# Power.net
KiCad netlist of a schematic drawn in Altium Designer
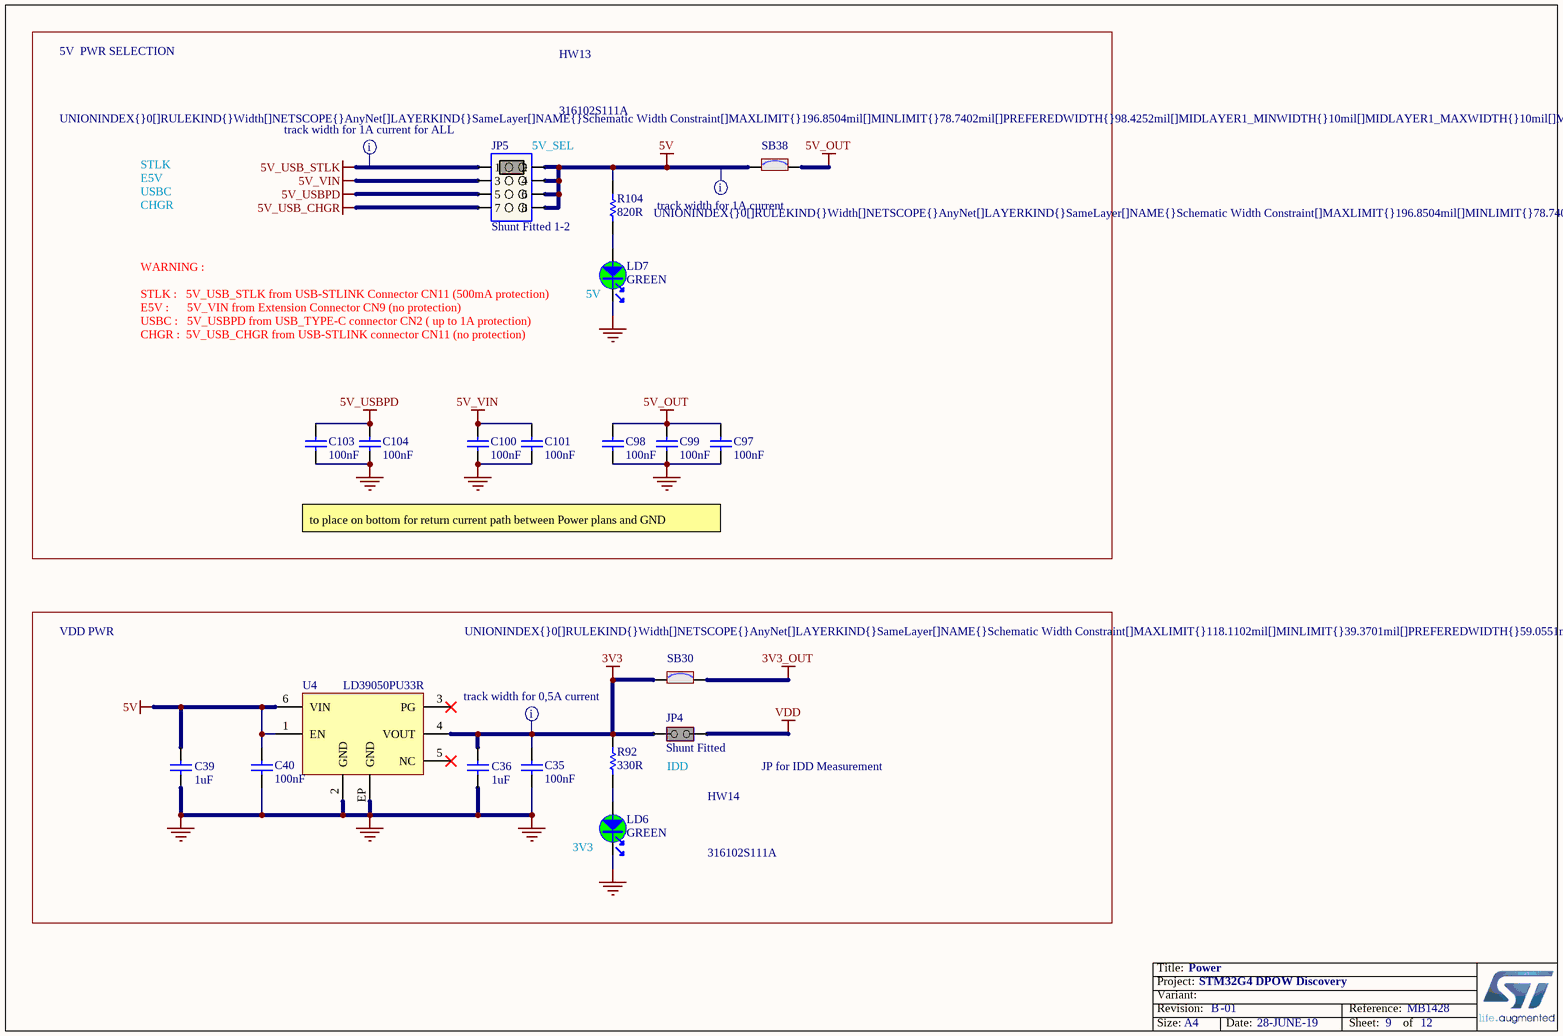
[diagram p0: Power.SchDoc]

(export (version "E")
  (design (tool "Eeschema 10.0.6"))
  (components
    (comp (ref "C35")
      (value "100nF")
      (footprint "C0402")
      (description "Capacitor, MLCC, 100nF, 16V, X7R, 10%, 0402, T=0,5mm")
      (fields
        (field (name "INTERNAL_PART_NUMBER") "MCD-00102")
        (field (name "MANUFACTURER_PART_NUMBER") "CC0402KRX7R7BB104")
        (field (name "PROVIDED_BY") "SUBCO")
      )
      (libsource (lib "MCD_PARTS_database") (part "Capacitor"))
    )
    (comp (ref "C36")
      (value "1uF")
      (footprint "C0603")
      (description "Capacitor, MLCC, 1uF, 16V, X5R, 10%, 0603, T=0,8mm")
      (fields
        (field (name "INTERNAL_PART_NUMBER") "MCD-00010")
        (field (name "MANUFACTURER_PART_NUMBER") "CC0603KRX5R7BB105")
        (field (name "PROVIDED_BY") "SUBCO")
      )
      (libsource (lib "MCD_PARTS_database") (part "Capacitor"))
    )
    (comp (ref "C39")
      (value "1uF")
      (footprint "C0603")
      (description "Capacitor, MLCC, 1uF, 16V, X5R, 10%, 0603, T=0,8mm")
      (fields
        (field (name "INTERNAL_PART_NUMBER") "MCD-00010")
        (field (name "MANUFACTURER_PART_NUMBER") "CC0603KRX5R7BB105")
        (field (name "PROVIDED_BY") "SUBCO")
      )
      (libsource (lib "MCD_PARTS_database") (part "Capacitor"))
    )
    (comp (ref "C40")
      (value "100nF")
      (footprint "C0402")
      (description "Capacitor, MLCC, 100nF, 16V, X7R, 10%, 0402, T=0,5mm")
      (fields
        (field (name "INTERNAL_PART_NUMBER") "MCD-00102")
        (field (name "MANUFACTURER_PART_NUMBER") "CC0402KRX7R7BB104")
        (field (name "PROVIDED_BY") "SUBCO")
      )
      (libsource (lib "MCD_PARTS_database") (part "Capacitor"))
    )
    (comp (ref "C97")
      (value "100nF")
      (footprint "C0402")
      (description "Capacitor, MLCC, 100nF, 16V, X7R, 10%, 0402, T=0,5mm")
      (fields
        (field (name "INTERNAL_PART_NUMBER") "MCD-00102")
        (field (name "MANUFACTURER_PART_NUMBER") "CC0402KRX7R7BB104")
        (field (name "PROVIDED_BY") "SUBCO")
      )
      (libsource (lib "MCD_PARTS_database") (part "Capacitor"))
    )
    (comp (ref "C98")
      (value "100nF")
      (footprint "C0402")
      (description "Capacitor, MLCC, 100nF, 16V, X7R, 10%, 0402, T=0,5mm")
      (fields
        (field (name "INTERNAL_PART_NUMBER") "MCD-00102")
        (field (name "MANUFACTURER_PART_NUMBER") "CC0402KRX7R7BB104")
        (field (name "PROVIDED_BY") "SUBCO")
      )
      (libsource (lib "MCD_PARTS_database") (part "Capacitor"))
    )
    (comp (ref "C99")
      (value "100nF")
      (footprint "C0402")
      (description "Capacitor, MLCC, 100nF, 16V, X7R, 10%, 0402, T=0,5mm")
      (fields
        (field (name "INTERNAL_PART_NUMBER") "MCD-00102")
        (field (name "MANUFACTURER_PART_NUMBER") "CC0402KRX7R7BB104")
        (field (name "PROVIDED_BY") "SUBCO")
      )
      (libsource (lib "MCD_PARTS_database") (part "Capacitor"))
    )
    (comp (ref "C100")
      (value "100nF")
      (footprint "C0402")
      (description "Capacitor, MLCC, 100nF, 16V, X7R, 10%, 0402, T=0,5mm")
      (fields
        (field (name "INTERNAL_PART_NUMBER") "MCD-00102")
        (field (name "MANUFACTURER_PART_NUMBER") "CC0402KRX7R7BB104")
        (field (name "PROVIDED_BY") "SUBCO")
      )
      (libsource (lib "MCD_PARTS_database") (part "Capacitor"))
    )
    (comp (ref "C101")
      (value "100nF")
      (footprint "C0402")
      (description "Capacitor, MLCC, 100nF, 16V, X7R, 10%, 0402, T=0,5mm")
      (fields
        (field (name "INTERNAL_PART_NUMBER") "MCD-00102")
        (field (name "MANUFACTURER_PART_NUMBER") "CC0402KRX7R7BB104")
        (field (name "PROVIDED_BY") "SUBCO")
      )
      (libsource (lib "MCD_PARTS_database") (part "Capacitor"))
    )
    (comp (ref "C103")
      (value "100nF")
      (footprint "C0402")
      (description "Capacitor, MLCC, 100nF, 16V, X7R, 10%, 0402, T=0,5mm")
      (fields
        (field (name "INTERNAL_PART_NUMBER") "MCD-00102")
        (field (name "MANUFACTURER_PART_NUMBER") "CC0402KRX7R7BB104")
        (field (name "PROVIDED_BY") "SUBCO")
      )
      (libsource (lib "MCD_PARTS_database") (part "Capacitor"))
    )
    (comp (ref "C104")
      (value "100nF")
      (footprint "C0402")
      (description "Capacitor, MLCC, 100nF, 16V, X7R, 10%, 0402, T=0,5mm")
      (fields
        (field (name "INTERNAL_PART_NUMBER") "MCD-00102")
        (field (name "MANUFACTURER_PART_NUMBER") "CC0402KRX7R7BB104")
        (field (name "PROVIDED_BY") "SUBCO")
      )
      (libsource (lib "MCD_PARTS_database") (part "Capacitor"))
    )
    (comp (ref "HW13")
      (value "316102S111A")
      (description "Jumper, height 6mm, Black, 2.54mm, 3A, 20 mohm, open")
      (fields
        (field (name "INTERNAL_PART_NUMBER") "MCD-01849")
        (field (name "MANUFACTURER") "JIUBABA")
        (field (name "PROVIDED_BY") "SUBCO")
      )
      (libsource (lib "MCD_PARTS_database") (part "JUMPER_OPEN"))
    )
    (comp (ref "HW14")
      (value "316102S111A")
      (description "Jumper, height 6mm, Black, 2.54mm, 3A, 20 mohm, open")
      (fields
        (field (name "INTERNAL_PART_NUMBER") "MCD-01849")
        (field (name "MANUFACTURER") "JIUBABA")
        (field (name "PROVIDED_BY") "SUBCO")
      )
      (libsource (lib "MCD_PARTS_database") (part "JUMPER_OPEN"))
    )
    (comp (ref "JP4")
      (value "Shunt Fitted")
      (footprint "CON_988-JIUBABA_313102S111116")
      (description "Header 2x1, 2.54mm, VR, TH, height 6 mm / 3 mm, total 11.6mm - Shunt Fitted by default")
      (fields
        (field (name "INTERNAL_PART_NUMBER") "MCD-01662")
        (field (name "MANUFACTURER_PART_NUMBER") "313102S111116")
        (field (name "PROVIDED_BY") "SUBCO")
      )
      (libsource (lib "MCD_PARTS_database") (part "Jumper_Header 2x1 Fitted"))
    )
    (comp (ref "JP5")
      (value "Shunt Fitted 1-2")
      (footprint "CON_988-JIUBABA_313208S141116")
      (description "Header, 4x2, 2,54mm, VR, TH, Height 6mm/3m, total 11.6mm - Shunt Fitted 1-2")
      (fields
        (field (name "INTERNAL_PART_NUMBER") "MCD-01661")
        (field (name "MANUFACTURER_PART_NUMBER") "313208S141116")
        (field (name "PROVIDED_BY") "SUBCO")
      )
      (libsource (lib "MCD_PARTS_database") (part "Jumper_Header 4x2 Fitted 1-2"))
    )
    (comp (ref "LD6")
      (value "GREEN")
      (footprint "LED_0603_GREEN")
      (description "LED, Green, 0603")
      (fields
        (field (name "INTERNAL_PART_NUMBER") "MCD-00050")
        (field (name "MANUFACTURER_PART_NUMBER") "19-213SYGC/S530-E2/TR8")
        (field (name "PROVIDED_BY") "SUBCO")
      )
      (libsource (lib "MCD_PARTS_database") (part "LED_green"))
    )
    (comp (ref "LD7")
      (value "GREEN")
      (footprint "LED_0603_GREEN")
      (description "LED, Green, 0603")
      (fields
        (field (name "INTERNAL_PART_NUMBER") "MCD-00050")
        (field (name "MANUFACTURER_PART_NUMBER") "19-213SYGC/S530-E2/TR8")
        (field (name "PROVIDED_BY") "SUBCO")
      )
      (libsource (lib "MCD_PARTS_database") (part "LED_green"))
    )
    (comp (ref "R92")
      (value "330R")
      (footprint "R0603")
      (description "Resistor,330R,0603,1%,1/10W")
      (fields
        (field (name "INTERNAL_PART_NUMBER") "MCD-00197")
        (field (name "MANUFACTURER_PART_NUMBER") "RC0603FR-07330RL")
        (field (name "PROVIDED_BY") "SUBCO")
      )
      (libsource (lib "MCD_PARTS_database") (part "Resistor"))
    )
    (comp (ref "R104")
      (value "820R")
      (footprint "R0603")
      (description "Resistor,820R,0603,1%,1/10W")
      (fields
        (field (name "INTERNAL_PART_NUMBER") "MCD-00528")
        (field (name "MANUFACTURER_PART_NUMBER") "RC0603FR-07820RL")
        (field (name "PROVIDED_BY") "SUBCO")
      )
      (libsource (lib "MCD_PARTS_database") (part "Resistor"))
    )
    (comp (ref "SB30")
      (value "~")
      (footprint "SOLDER-BRIDGE_R0603-0R")
      (description "Solder Bridge ON")
      (fields
        (field (name "INTERNAL_PART_NUMBER") "MCD-00071")
        (field (name "MANUFACTURER_PART_NUMBER") "RC0603JR-070RL")
        (field (name "PROVIDED_BY") "SUBCO")
      )
      (libsource (lib "MCD_PARTS_database") (part "SB_ON"))
    )
    (comp (ref "SB38")
      (value "~")
      (footprint "SOLDER-BRIDGE_R0603-0R")
      (description "Solder Bridge ON")
      (fields
        (field (name "INTERNAL_PART_NUMBER") "MCD-00071")
        (field (name "MANUFACTURER_PART_NUMBER") "RC0603JR-070RL")
        (field (name "PROVIDED_BY") "SUBCO")
      )
      (libsource (lib "MCD_PARTS_database") (part "SB_ON"))
    )
    (comp (ref "U4")
      (value "LD39050PU33R")
      (footprint "ICC_DFN6-EPAD_3X3_P095")
      (description "Low quiescent current and low noise voltage regulators")
      (fields
        (field (name "INTERNAL_PART_NUMBER") "MCD-00215")
        (field (name "MANUFACTURER") "STMICROELECTRONICS")
        (field (name "PROVIDED_BY") "SUBCO with ST control")
      )
      (libsource (lib "MCD_PARTS_database") (part "LD39050PU33R"))
    )
  )
  (nets
    (net (code "1") (name "3V3") (class "Default")
      (node (ref "C35") (pin "2") (pinfunction "2_2") (pintype "passive"))
      (node (ref "C36") (pin "2") (pinfunction "2_2") (pintype "passive"))
      (node (ref "JP4") (pin "1") (pinfunction "COMMON_1") (pintype "passive"))
      (node (ref "R92") (pin "2") (pinfunction "2_2") (pintype "passive"))
      (node (ref "SB30") (pin "1") (pinfunction "1_1") (pintype "passive"))
      (node (ref "U4") (pin "4") (pinfunction "VOUT_4") (pintype "passive"))
    )
    (net (code "2") (name "3V3_OUT") (class "Default")
      (node (ref "SB30") (pin "2") (pinfunction "2_2") (pintype "passive"))
    )
    (net (code "3") (name "5V") (class "Default")
      (node (ref "C39") (pin "2") (pinfunction "2_2") (pintype "passive"))
      (node (ref "C40") (pin "2") (pinfunction "2_2") (pintype "passive"))
      (node (ref "JP5") (pin "2") (pinfunction "2_2") (pintype "passive"))
      (node (ref "JP5") (pin "4") (pinfunction "4_4") (pintype "passive"))
      (node (ref "JP5") (pin "6") (pinfunction "6_6") (pintype "passive"))
      (node (ref "JP5") (pin "8") (pinfunction "8_8") (pintype "passive"))
      (node (ref "R104") (pin "2") (pinfunction "2_2") (pintype "passive"))
      (node (ref "SB38") (pin "1") (pinfunction "1_1") (pintype "passive"))
      (node (ref "U4") (pin "1") (pinfunction "EN_1") (pintype "passive"))
      (node (ref "U4") (pin "6") (pinfunction "VIN_6") (pintype "passive"))
    )
    (net (code "4") (name "5V_OUT") (class "Default")
      (node (ref "C97") (pin "2") (pinfunction "2_2") (pintype "passive"))
      (node (ref "C98") (pin "2") (pinfunction "2_2") (pintype "passive"))
      (node (ref "C99") (pin "2") (pinfunction "2_2") (pintype "passive"))
      (node (ref "SB38") (pin "2") (pinfunction "2_2") (pintype "passive"))
    )
    (net (code "5") (name "5V_USBPD") (class "Default")
      (node (ref "C103") (pin "2") (pinfunction "2_2") (pintype "passive"))
      (node (ref "C104") (pin "2") (pinfunction "2_2") (pintype "passive"))
      (node (ref "JP5") (pin "5") (pinfunction "5_5") (pintype "passive"))
    )
    (net (code "6") (name "5V_USB_CHGR") (class "Default")
      (node (ref "JP5") (pin "7") (pinfunction "7_7") (pintype "passive"))
    )
    (net (code "7") (name "5V_USB_STLK") (class "Default")
      (node (ref "JP5") (pin "1") (pinfunction "1_1") (pintype "passive"))
    )
    (net (code "8") (name "5V_VIN") (class "Default")
      (node (ref "C100") (pin "2") (pinfunction "2_2") (pintype "passive"))
      (node (ref "C101") (pin "2") (pinfunction "2_2") (pintype "passive"))
      (node (ref "JP5") (pin "3") (pinfunction "3_3") (pintype "passive"))
    )
    (net (code "9") (name "GND") (class "Default")
      (node (ref "C100") (pin "1") (pinfunction "1_1") (pintype "passive"))
      (node (ref "C101") (pin "1") (pinfunction "1_1") (pintype "passive"))
      (node (ref "C103") (pin "1") (pinfunction "1_1") (pintype "passive"))
      (node (ref "C104") (pin "1") (pinfunction "1_1") (pintype "passive"))
      (node (ref "C35") (pin "1") (pinfunction "1_1") (pintype "passive"))
      (node (ref "C36") (pin "1") (pinfunction "1_1") (pintype "passive"))
      (node (ref "C39") (pin "1") (pinfunction "1_1") (pintype "passive"))
      (node (ref "C40") (pin "1") (pinfunction "1_1") (pintype "passive"))
      (node (ref "C97") (pin "1") (pinfunction "1_1") (pintype "passive"))
      (node (ref "C98") (pin "1") (pinfunction "1_1") (pintype "passive"))
      (node (ref "C99") (pin "1") (pinfunction "1_1") (pintype "passive"))
      (node (ref "LD6") (pin "2") (pintype "passive"))
      (node (ref "LD7") (pin "2") (pintype "passive"))
      (node (ref "U4") (pin "2") (pinfunction "GND_2") (pintype "passive"))
      (node (ref "U4") (pin "EP") (pinfunction "GND_EP") (pintype "passive"))
    )
    (net (code "10") (name "Net-(LD6-Pad1)") (class "Default")
      (node (ref "LD6") (pin "1") (pintype "passive"))
      (node (ref "R92") (pin "1") (pinfunction "1_1") (pintype "passive"))
    )
    (net (code "11") (name "Net-(LD7-Pad1)") (class "Default")
      (node (ref "LD7") (pin "1") (pintype "passive"))
      (node (ref "R104") (pin "1") (pinfunction "1_1") (pintype "passive"))
    )
    (net (code "12") (name "VDD") (class "Default")
      (node (ref "JP4") (pin "2") (pinfunction "NO_2") (pintype "passive"))
    )
    (net (code "13") (name "unconnected-(U4-NC-Pad5)") (class "Default")
      (node (ref "U4") (pin "5") (pinfunction "NC_5") (pintype "passive+no_connect"))
    )
    (net (code "14") (name "unconnected-(U4-PG-Pad3)") (class "Default")
      (node (ref "U4") (pin "3") (pinfunction "PG_3") (pintype "passive+no_connect"))
    )
  )
)
